# Control.net
KiCad netlist of a schematic drawn in EAGLE
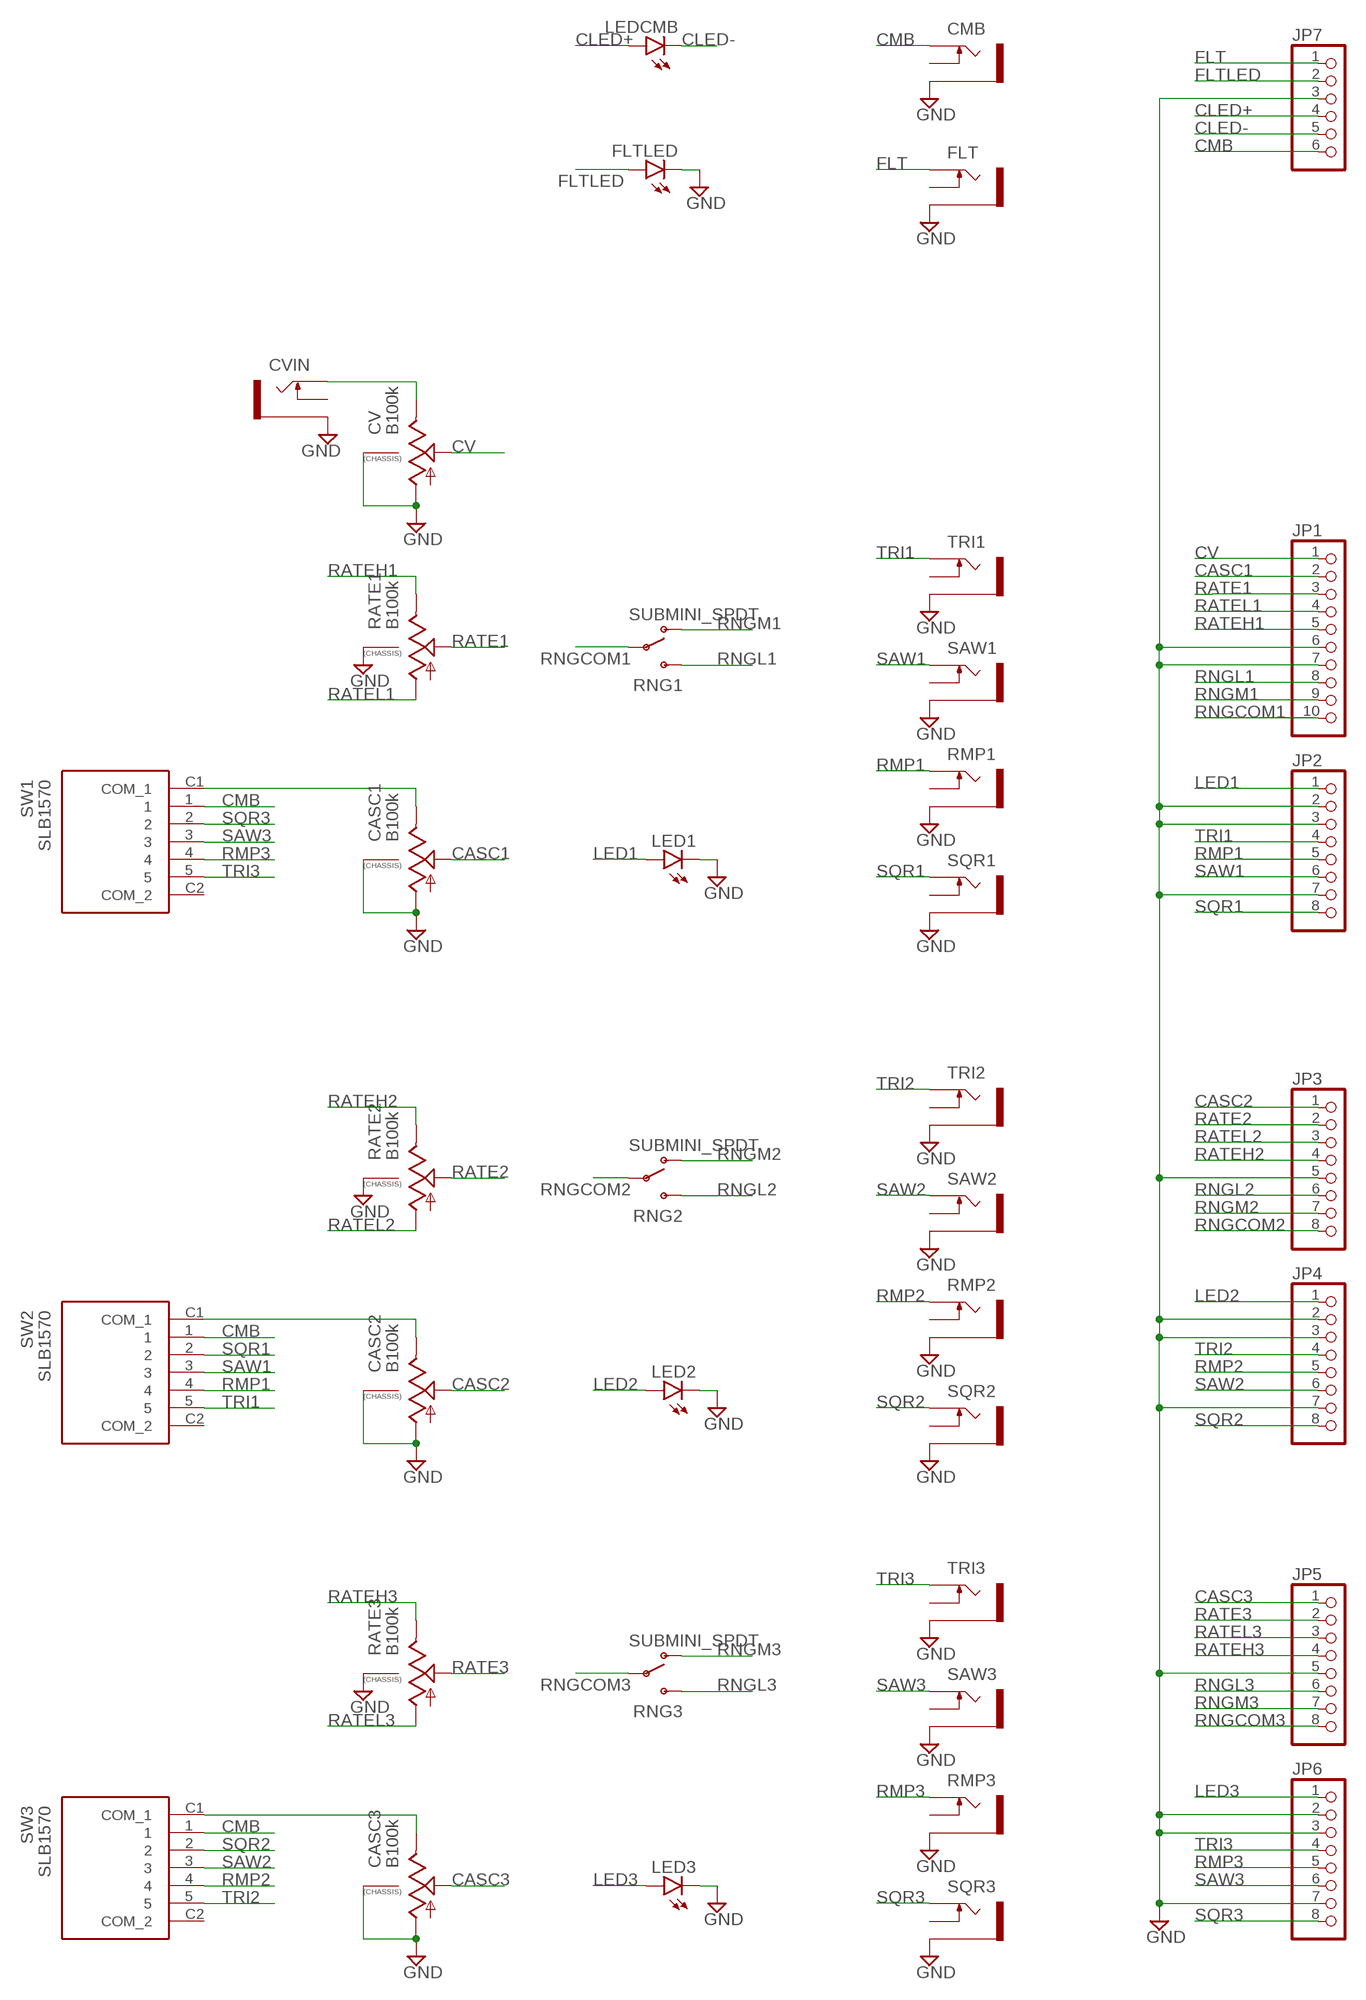
[diagram p0: schematic, sheet 1]

(export (version "E")
  (design (tool "Eeschema 10.0.6"))
  (components
    (comp (ref "CASC1")
      (value "B100k")
      (footprint "eagle-import:9MM_SNAP-IN_POT")
      (libsource (lib "eagle-import") (part "9MM_SNAP-IN_POT_CHASSIS"))
    )
    (comp (ref "CASC2")
      (value "B100k")
      (footprint "eagle-import:9MM_SNAP-IN_POT")
      (libsource (lib "eagle-import") (part "9MM_SNAP-IN_POT_CHASSIS"))
    )
    (comp (ref "CASC3")
      (value "B100k")
      (footprint "eagle-import:9MM_SNAP-IN_POT")
      (libsource (lib "eagle-import") (part "9MM_SNAP-IN_POT_CHASSIS"))
    )
    (comp (ref "CMB")
      (value "THONKICONNNEW")
      (footprint "eagle-import:WQP-PJ301M-12_JACK")
      (libsource (lib "eagle-import") (part "THONKICONNNEW"))
    )
    (comp (ref "CV")
      (value "B100k")
      (footprint "eagle-import:9MM_SNAP-IN_POT")
      (libsource (lib "eagle-import") (part "9MM_SNAP-IN_POT_CHASSIS"))
    )
    (comp (ref "CVIN")
      (value "THONKICONNNEW")
      (footprint "eagle-import:WQP-PJ301M-12_JACK")
      (libsource (lib "eagle-import") (part "THONKICONNNEW"))
    )
    (comp (ref "FLT")
      (value "THONKICONNNEW")
      (footprint "eagle-import:WQP-PJ301M-12_JACK")
      (libsource (lib "eagle-import") (part "THONKICONNNEW"))
    )
    (comp (ref "FLTLED")
      (value "LED3MM")
      (footprint "eagle-import:LED3MM")
      (libsource (lib "eagle-import") (part "LED3MM"))
    )
    (comp (ref "JP1")
      (value "PINHD-1X10")
      (footprint "eagle-import:1X10")
      (libsource (lib "eagle-import") (part "PINHD-1X10"))
    )
    (comp (ref "JP2")
      (value "PINHD-1X8")
      (footprint "eagle-import:1X08")
      (libsource (lib "eagle-import") (part "PINHD-1X8"))
    )
    (comp (ref "JP3")
      (value "PINHD-1X8")
      (footprint "eagle-import:1X08")
      (libsource (lib "eagle-import") (part "PINHD-1X8"))
    )
    (comp (ref "JP4")
      (value "PINHD-1X8")
      (footprint "eagle-import:1X08")
      (libsource (lib "eagle-import") (part "PINHD-1X8"))
    )
    (comp (ref "JP5")
      (value "PINHD-1X8")
      (footprint "eagle-import:1X08")
      (libsource (lib "eagle-import") (part "PINHD-1X8"))
    )
    (comp (ref "JP6")
      (value "PINHD-1X8")
      (footprint "eagle-import:1X08")
      (libsource (lib "eagle-import") (part "PINHD-1X8"))
    )
    (comp (ref "JP7")
      (value "PINHD-1X6")
      (footprint "eagle-import:1X06")
      (libsource (lib "eagle-import") (part "PINHD-1X6"))
    )
    (comp (ref "LED1")
      (value "LED3MM")
      (footprint "eagle-import:LED3MM")
      (libsource (lib "eagle-import") (part "LED3MM"))
    )
    (comp (ref "LED2")
      (value "LED3MM")
      (footprint "eagle-import:LED3MM")
      (libsource (lib "eagle-import") (part "LED3MM"))
    )
    (comp (ref "LED3")
      (value "LED3MM")
      (footprint "eagle-import:LED3MM")
      (libsource (lib "eagle-import") (part "LED3MM"))
    )
    (comp (ref "LEDCMB")
      (value "LED3MM")
      (footprint "eagle-import:LED3MM")
      (libsource (lib "eagle-import") (part "LED3MM"))
    )
    (comp (ref "RATE1")
      (value "B100k")
      (footprint "eagle-import:9MM_SNAP-IN_POT")
      (libsource (lib "eagle-import") (part "9MM_SNAP-IN_POT_CHASSIS"))
    )
    (comp (ref "RATE2")
      (value "B100k")
      (footprint "eagle-import:9MM_SNAP-IN_POT")
      (libsource (lib "eagle-import") (part "9MM_SNAP-IN_POT_CHASSIS"))
    )
    (comp (ref "RATE3")
      (value "B100k")
      (footprint "eagle-import:9MM_SNAP-IN_POT")
      (libsource (lib "eagle-import") (part "9MM_SNAP-IN_POT_CHASSIS"))
    )
    (comp (ref "RMP1")
      (value "THONKICONNNEW")
      (footprint "eagle-import:WQP-PJ301M-12_JACK")
      (libsource (lib "eagle-import") (part "THONKICONNNEW"))
    )
    (comp (ref "RMP2")
      (value "THONKICONNNEW")
      (footprint "eagle-import:WQP-PJ301M-12_JACK")
      (libsource (lib "eagle-import") (part "THONKICONNNEW"))
    )
    (comp (ref "RMP3")
      (value "THONKICONNNEW")
      (footprint "eagle-import:WQP-PJ301M-12_JACK")
      (libsource (lib "eagle-import") (part "THONKICONNNEW"))
    )
    (comp (ref "RNG1")
      (value "SUBMINI_SPDT")
      (footprint "eagle-import:SUBMINI_TOGGLE")
      (libsource (lib "eagle-import") (part "SUBMINI_SPDT"))
    )
    (comp (ref "RNG2")
      (value "SUBMINI_SPDT")
      (footprint "eagle-import:SUBMINI_TOGGLE")
      (libsource (lib "eagle-import") (part "SUBMINI_SPDT"))
    )
    (comp (ref "RNG3")
      (value "SUBMINI_SPDT")
      (footprint "eagle-import:SUBMINI_TOGGLE")
      (libsource (lib "eagle-import") (part "SUBMINI_SPDT"))
    )
    (comp (ref "SAW1")
      (value "THONKICONNNEW")
      (footprint "eagle-import:WQP-PJ301M-12_JACK")
      (libsource (lib "eagle-import") (part "THONKICONNNEW"))
    )
    (comp (ref "SAW2")
      (value "THONKICONNNEW")
      (footprint "eagle-import:WQP-PJ301M-12_JACK")
      (libsource (lib "eagle-import") (part "THONKICONNNEW"))
    )
    (comp (ref "SAW3")
      (value "THONKICONNNEW")
      (footprint "eagle-import:WQP-PJ301M-12_JACK")
      (libsource (lib "eagle-import") (part "THONKICONNNEW"))
    )
    (comp (ref "SQR1")
      (value "THONKICONNNEW")
      (footprint "eagle-import:WQP-PJ301M-12_JACK")
      (libsource (lib "eagle-import") (part "THONKICONNNEW"))
    )
    (comp (ref "SQR2")
      (value "THONKICONNNEW")
      (footprint "eagle-import:WQP-PJ301M-12_JACK")
      (libsource (lib "eagle-import") (part "THONKICONNNEW"))
    )
    (comp (ref "SQR3")
      (value "THONKICONNNEW")
      (footprint "eagle-import:WQP-PJ301M-12_JACK")
      (libsource (lib "eagle-import") (part "THONKICONNNEW"))
    )
    (comp (ref "SW1")
      (value "SLB1570")
      (footprint "eagle-import:SLB1570")
      (fields (field (name "MOUSER_PART_NUMBER") "642-SLB1570"))
      (libsource (lib "eagle-import") (part "SLB1570"))
    )
    (comp (ref "SW2")
      (value "SLB1570")
      (footprint "eagle-import:SLB1570")
      (fields (field (name "MOUSER_PART_NUMBER") "642-SLB1570"))
      (libsource (lib "eagle-import") (part "SLB1570"))
    )
    (comp (ref "SW3")
      (value "SLB1570")
      (footprint "eagle-import:SLB1570")
      (fields (field (name "MOUSER_PART_NUMBER") "642-SLB1570"))
      (libsource (lib "eagle-import") (part "SLB1570"))
    )
    (comp (ref "TRI1")
      (value "THONKICONNNEW")
      (footprint "eagle-import:WQP-PJ301M-12_JACK")
      (libsource (lib "eagle-import") (part "THONKICONNNEW"))
    )
    (comp (ref "TRI2")
      (value "THONKICONNNEW")
      (footprint "eagle-import:WQP-PJ301M-12_JACK")
      (libsource (lib "eagle-import") (part "THONKICONNNEW"))
    )
    (comp (ref "TRI3")
      (value "THONKICONNNEW")
      (footprint "eagle-import:WQP-PJ301M-12_JACK")
      (libsource (lib "eagle-import") (part "THONKICONNNEW"))
    )
  )
  (nets
    (net (code "1") (name "/CASC1") (class "Default")
      (node (ref "CASC1") (pin "2") (pinfunction "S_2") (pintype "passive"))
      (node (ref "JP1") (pin "2") (pinfunction "2_2") (pintype "passive"))
    )
    (net (code "2") (name "/CASC2") (class "Default")
      (node (ref "CASC2") (pin "2") (pinfunction "S_2") (pintype "passive"))
      (node (ref "JP3") (pin "1") (pinfunction "1_1") (pintype "passive"))
    )
    (net (code "3") (name "/CASC3") (class "Default")
      (node (ref "CASC3") (pin "2") (pinfunction "S_2") (pintype "passive"))
      (node (ref "JP5") (pin "1") (pinfunction "1_1") (pintype "passive"))
    )
    (net (code "4") (name "/CLED+") (class "Default")
      (node (ref "JP7") (pin "4") (pinfunction "4_4") (pintype "passive"))
      (node (ref "LEDCMB") (pin "A") (pinfunction "A_A") (pintype "passive"))
    )
    (net (code "5") (name "/CLED-") (class "Default")
      (node (ref "JP7") (pin "5") (pinfunction "5_5") (pintype "passive"))
      (node (ref "LEDCMB") (pin "K") (pinfunction "C_K") (pintype "passive"))
    )
    (net (code "6") (name "/CMB") (class "Default")
      (node (ref "CMB") (pin "P$1_TIP") (pinfunction "TIP_P$1_TIP") (pintype "passive"))
      (node (ref "JP7") (pin "6") (pinfunction "6_6") (pintype "passive"))
      (node (ref "SW1") (pin "1") (pinfunction "1_1") (pintype "bidirectional"))
      (node (ref "SW2") (pin "1") (pinfunction "1_1") (pintype "bidirectional"))
      (node (ref "SW3") (pin "1") (pinfunction "1_1") (pintype "bidirectional"))
    )
    (net (code "7") (name "/CV") (class "Default")
      (node (ref "CV") (pin "2") (pinfunction "S_2") (pintype "passive"))
      (node (ref "JP1") (pin "1") (pinfunction "1_1") (pintype "passive"))
    )
    (net (code "8") (name "/FLT") (class "Default")
      (node (ref "FLT") (pin "P$1_TIP") (pinfunction "TIP_P$1_TIP") (pintype "passive"))
      (node (ref "JP7") (pin "1") (pinfunction "1_1") (pintype "passive"))
    )
    (net (code "9") (name "/FLTLED") (class "Default")
      (node (ref "FLTLED") (pin "A") (pinfunction "A_A") (pintype "passive"))
      (node (ref "JP7") (pin "2") (pinfunction "2_2") (pintype "passive"))
    )
    (net (code "10") (name "/LED1") (class "Default")
      (node (ref "JP2") (pin "1") (pinfunction "1_1") (pintype "passive"))
      (node (ref "LED1") (pin "A") (pinfunction "A_A") (pintype "passive"))
    )
    (net (code "11") (name "/LED2") (class "Default")
      (node (ref "JP4") (pin "1") (pinfunction "1_1") (pintype "passive"))
      (node (ref "LED2") (pin "A") (pinfunction "A_A") (pintype "passive"))
    )
    (net (code "12") (name "/LED3") (class "Default")
      (node (ref "JP6") (pin "1") (pinfunction "1_1") (pintype "passive"))
      (node (ref "LED3") (pin "A") (pinfunction "A_A") (pintype "passive"))
    )
    (net (code "13") (name "/RATE1") (class "Default")
      (node (ref "JP1") (pin "3") (pinfunction "3_3") (pintype "passive"))
      (node (ref "RATE1") (pin "2") (pinfunction "S_2") (pintype "passive"))
    )
    (net (code "14") (name "/RATE2") (class "Default")
      (node (ref "JP3") (pin "2") (pinfunction "2_2") (pintype "passive"))
      (node (ref "RATE2") (pin "2") (pinfunction "S_2") (pintype "passive"))
    )
    (net (code "15") (name "/RATE3") (class "Default")
      (node (ref "JP5") (pin "2") (pinfunction "2_2") (pintype "passive"))
      (node (ref "RATE3") (pin "2") (pinfunction "S_2") (pintype "passive"))
    )
    (net (code "16") (name "/RATEH1") (class "Default")
      (node (ref "JP1") (pin "5") (pinfunction "5_5") (pintype "passive"))
      (node (ref "RATE1") (pin "3") (pinfunction "E_3") (pintype "passive"))
    )
    (net (code "17") (name "/RATEH2") (class "Default")
      (node (ref "JP3") (pin "4") (pinfunction "4_4") (pintype "passive"))
      (node (ref "RATE2") (pin "3") (pinfunction "E_3") (pintype "passive"))
    )
    (net (code "18") (name "/RATEH3") (class "Default")
      (node (ref "JP5") (pin "4") (pinfunction "4_4") (pintype "passive"))
      (node (ref "RATE3") (pin "3") (pinfunction "E_3") (pintype "passive"))
    )
    (net (code "19") (name "/RATEL1") (class "Default")
      (node (ref "JP1") (pin "4") (pinfunction "4_4") (pintype "passive"))
      (node (ref "RATE1") (pin "1") (pinfunction "A_1") (pintype "passive"))
    )
    (net (code "20") (name "/RATEL2") (class "Default")
      (node (ref "JP3") (pin "3") (pinfunction "3_3") (pintype "passive"))
      (node (ref "RATE2") (pin "1") (pinfunction "A_1") (pintype "passive"))
    )
    (net (code "21") (name "/RATEL3") (class "Default")
      (node (ref "JP5") (pin "3") (pinfunction "3_3") (pintype "passive"))
      (node (ref "RATE3") (pin "1") (pinfunction "A_1") (pintype "passive"))
    )
    (net (code "22") (name "/RMP1") (class "Default")
      (node (ref "JP2") (pin "5") (pinfunction "5_5") (pintype "passive"))
      (node (ref "RMP1") (pin "P$1_TIP") (pinfunction "TIP_P$1_TIP") (pintype "passive"))
      (node (ref "SW2") (pin "4") (pinfunction "4_4") (pintype "bidirectional"))
    )
    (net (code "23") (name "/RMP2") (class "Default")
      (node (ref "JP4") (pin "5") (pinfunction "5_5") (pintype "passive"))
      (node (ref "RMP2") (pin "P$1_TIP") (pinfunction "TIP_P$1_TIP") (pintype "passive"))
      (node (ref "SW3") (pin "4") (pinfunction "4_4") (pintype "bidirectional"))
    )
    (net (code "24") (name "/RMP3") (class "Default")
      (node (ref "JP6") (pin "5") (pinfunction "5_5") (pintype "passive"))
      (node (ref "RMP3") (pin "P$1_TIP") (pinfunction "TIP_P$1_TIP") (pintype "passive"))
      (node (ref "SW1") (pin "4") (pinfunction "4_4") (pintype "bidirectional"))
    )
    (net (code "25") (name "/RNGCOM1") (class "Default")
      (node (ref "JP1") (pin "10") (pinfunction "10_10") (pintype "passive"))
      (node (ref "RNG1") (pin "COM") (pinfunction "COMMON_COM") (pintype "passive"))
    )
    (net (code "26") (name "/RNGCOM2") (class "Default")
      (node (ref "JP3") (pin "8") (pinfunction "8_8") (pintype "passive"))
      (node (ref "RNG2") (pin "COM") (pinfunction "COMMON_COM") (pintype "passive"))
    )
    (net (code "27") (name "/RNGCOM3") (class "Default")
      (node (ref "JP5") (pin "8") (pinfunction "8_8") (pintype "passive"))
      (node (ref "RNG3") (pin "COM") (pinfunction "COMMON_COM") (pintype "passive"))
    )
    (net (code "28") (name "/RNGL1") (class "Default")
      (node (ref "JP1") (pin "8") (pinfunction "8_8") (pintype "passive"))
      (node (ref "RNG1") (pin "3") (pinfunction "S_3") (pintype "passive"))
    )
    (net (code "29") (name "/RNGL2") (class "Default")
      (node (ref "JP3") (pin "6") (pinfunction "6_6") (pintype "passive"))
      (node (ref "RNG2") (pin "3") (pinfunction "S_3") (pintype "passive"))
    )
    (net (code "30") (name "/RNGL3") (class "Default")
      (node (ref "JP5") (pin "6") (pinfunction "6_6") (pintype "passive"))
      (node (ref "RNG3") (pin "3") (pinfunction "S_3") (pintype "passive"))
    )
    (net (code "31") (name "/RNGM1") (class "Default")
      (node (ref "JP1") (pin "9") (pinfunction "9_9") (pintype "passive"))
      (node (ref "RNG1") (pin "1") (pinfunction "O_1") (pintype "passive"))
    )
    (net (code "32") (name "/RNGM2") (class "Default")
      (node (ref "JP3") (pin "7") (pinfunction "7_7") (pintype "passive"))
      (node (ref "RNG2") (pin "1") (pinfunction "O_1") (pintype "passive"))
    )
    (net (code "33") (name "/RNGM3") (class "Default")
      (node (ref "JP5") (pin "7") (pinfunction "7_7") (pintype "passive"))
      (node (ref "RNG3") (pin "1") (pinfunction "O_1") (pintype "passive"))
    )
    (net (code "34") (name "/SAW1") (class "Default")
      (node (ref "JP2") (pin "6") (pinfunction "6_6") (pintype "passive"))
      (node (ref "SAW1") (pin "P$1_TIP") (pinfunction "TIP_P$1_TIP") (pintype "passive"))
      (node (ref "SW2") (pin "3") (pinfunction "3_3") (pintype "bidirectional"))
    )
    (net (code "35") (name "/SAW2") (class "Default")
      (node (ref "JP4") (pin "6") (pinfunction "6_6") (pintype "passive"))
      (node (ref "SAW2") (pin "P$1_TIP") (pinfunction "TIP_P$1_TIP") (pintype "passive"))
      (node (ref "SW3") (pin "3") (pinfunction "3_3") (pintype "bidirectional"))
    )
    (net (code "36") (name "/SAW3") (class "Default")
      (node (ref "JP6") (pin "6") (pinfunction "6_6") (pintype "passive"))
      (node (ref "SAW3") (pin "P$1_TIP") (pinfunction "TIP_P$1_TIP") (pintype "passive"))
      (node (ref "SW1") (pin "3") (pinfunction "3_3") (pintype "bidirectional"))
    )
    (net (code "37") (name "/SQR1") (class "Default")
      (node (ref "JP2") (pin "8") (pinfunction "8_8") (pintype "passive"))
      (node (ref "SQR1") (pin "P$1_TIP") (pinfunction "TIP_P$1_TIP") (pintype "passive"))
      (node (ref "SW2") (pin "2") (pinfunction "2_2") (pintype "bidirectional"))
    )
    (net (code "38") (name "/SQR2") (class "Default")
      (node (ref "JP4") (pin "8") (pinfunction "8_8") (pintype "passive"))
      (node (ref "SQR2") (pin "P$1_TIP") (pinfunction "TIP_P$1_TIP") (pintype "passive"))
      (node (ref "SW3") (pin "2") (pinfunction "2_2") (pintype "bidirectional"))
    )
    (net (code "39") (name "/SQR3") (class "Default")
      (node (ref "JP6") (pin "8") (pinfunction "8_8") (pintype "passive"))
      (node (ref "SQR3") (pin "P$1_TIP") (pinfunction "TIP_P$1_TIP") (pintype "passive"))
      (node (ref "SW1") (pin "2") (pinfunction "2_2") (pintype "bidirectional"))
    )
    (net (code "40") (name "/TRI1") (class "Default")
      (node (ref "JP2") (pin "4") (pinfunction "4_4") (pintype "passive"))
      (node (ref "SW2") (pin "5") (pinfunction "5_5") (pintype "bidirectional"))
      (node (ref "TRI1") (pin "P$1_TIP") (pinfunction "TIP_P$1_TIP") (pintype "passive"))
    )
    (net (code "41") (name "/TRI2") (class "Default")
      (node (ref "JP4") (pin "4") (pinfunction "4_4") (pintype "passive"))
      (node (ref "SW3") (pin "5") (pinfunction "5_5") (pintype "bidirectional"))
      (node (ref "TRI2") (pin "P$1_TIP") (pinfunction "TIP_P$1_TIP") (pintype "passive"))
    )
    (net (code "42") (name "/TRI3") (class "Default")
      (node (ref "JP6") (pin "4") (pinfunction "4_4") (pintype "passive"))
      (node (ref "SW1") (pin "5") (pinfunction "5_5") (pintype "bidirectional"))
      (node (ref "TRI3") (pin "P$1_TIP") (pinfunction "TIP_P$1_TIP") (pintype "passive"))
    )
    (net (code "43") (name "GND") (class "Default")
      (node (ref "CASC1") (pin "1") (pinfunction "A_1") (pintype "passive"))
      (node (ref "CASC1") (pin "CHASSIS1") (pinfunction "P$1_CHASSIS1") (pintype "passive"))
      (node (ref "CASC1") (pin "CHASSIS2") (pinfunction "P$1_CHASSIS2") (pintype "passive"))
      (node (ref "CASC2") (pin "1") (pinfunction "A_1") (pintype "passive"))
      (node (ref "CASC2") (pin "CHASSIS1") (pinfunction "P$1_CHASSIS1") (pintype "passive"))
      (node (ref "CASC2") (pin "CHASSIS2") (pinfunction "P$1_CHASSIS2") (pintype "passive"))
      (node (ref "CASC3") (pin "1") (pinfunction "A_1") (pintype "passive"))
      (node (ref "CASC3") (pin "CHASSIS1") (pinfunction "P$1_CHASSIS1") (pintype "passive"))
      (node (ref "CASC3") (pin "CHASSIS2") (pinfunction "P$1_CHASSIS2") (pintype "passive"))
      (node (ref "CMB") (pin "P$3_SLEEVE") (pinfunction "SLEEVE_P$3_SLEEVE") (pintype "passive"))
      (node (ref "CV") (pin "1") (pinfunction "A_1") (pintype "passive"))
      (node (ref "CV") (pin "CHASSIS1") (pinfunction "P$1_CHASSIS1") (pintype "passive"))
      (node (ref "CV") (pin "CHASSIS2") (pinfunction "P$1_CHASSIS2") (pintype "passive"))
      (node (ref "CVIN") (pin "P$3_SLEEVE") (pinfunction "SLEEVE_P$3_SLEEVE") (pintype "passive"))
      (node (ref "FLT") (pin "P$3_SLEEVE") (pinfunction "SLEEVE_P$3_SLEEVE") (pintype "passive"))
      (node (ref "FLTLED") (pin "K") (pinfunction "C_K") (pintype "passive"))
      (node (ref "JP1") (pin "6") (pinfunction "6_6") (pintype "passive"))
      (node (ref "JP1") (pin "7") (pinfunction "7_7") (pintype "passive"))
      (node (ref "JP2") (pin "2") (pinfunction "2_2") (pintype "passive"))
      (node (ref "JP2") (pin "3") (pinfunction "3_3") (pintype "passive"))
      (node (ref "JP2") (pin "7") (pinfunction "7_7") (pintype "passive"))
      (node (ref "JP3") (pin "5") (pinfunction "5_5") (pintype "passive"))
      (node (ref "JP4") (pin "2") (pinfunction "2_2") (pintype "passive"))
      (node (ref "JP4") (pin "3") (pinfunction "3_3") (pintype "passive"))
      (node (ref "JP4") (pin "7") (pinfunction "7_7") (pintype "passive"))
      (node (ref "JP5") (pin "5") (pinfunction "5_5") (pintype "passive"))
      (node (ref "JP6") (pin "2") (pinfunction "2_2") (pintype "passive"))
      (node (ref "JP6") (pin "3") (pinfunction "3_3") (pintype "passive"))
      (node (ref "JP6") (pin "7") (pinfunction "7_7") (pintype "passive"))
      (node (ref "JP7") (pin "3") (pinfunction "3_3") (pintype "passive"))
      (node (ref "LED1") (pin "K") (pinfunction "C_K") (pintype "passive"))
      (node (ref "LED2") (pin "K") (pinfunction "C_K") (pintype "passive"))
      (node (ref "LED3") (pin "K") (pinfunction "C_K") (pintype "passive"))
      (node (ref "RATE1") (pin "CHASSIS1") (pinfunction "P$1_CHASSIS1") (pintype "passive"))
      (node (ref "RATE1") (pin "CHASSIS2") (pinfunction "P$1_CHASSIS2") (pintype "passive"))
      (node (ref "RATE2") (pin "CHASSIS1") (pinfunction "P$1_CHASSIS1") (pintype "passive"))
      (node (ref "RATE2") (pin "CHASSIS2") (pinfunction "P$1_CHASSIS2") (pintype "passive"))
      (node (ref "RATE3") (pin "CHASSIS1") (pinfunction "P$1_CHASSIS1") (pintype "passive"))
      (node (ref "RATE3") (pin "CHASSIS2") (pinfunction "P$1_CHASSIS2") (pintype "passive"))
      (node (ref "RMP1") (pin "P$3_SLEEVE") (pinfunction "SLEEVE_P$3_SLEEVE") (pintype "passive"))
      (node (ref "RMP2") (pin "P$3_SLEEVE") (pinfunction "SLEEVE_P$3_SLEEVE") (pintype "passive"))
      (node (ref "RMP3") (pin "P$3_SLEEVE") (pinfunction "SLEEVE_P$3_SLEEVE") (pintype "passive"))
      (node (ref "SAW1") (pin "P$3_SLEEVE") (pinfunction "SLEEVE_P$3_SLEEVE") (pintype "passive"))
      (node (ref "SAW2") (pin "P$3_SLEEVE") (pinfunction "SLEEVE_P$3_SLEEVE") (pintype "passive"))
      (node (ref "SAW3") (pin "P$3_SLEEVE") (pinfunction "SLEEVE_P$3_SLEEVE") (pintype "passive"))
      (node (ref "SQR1") (pin "P$3_SLEEVE") (pinfunction "SLEEVE_P$3_SLEEVE") (pintype "passive"))
      (node (ref "SQR2") (pin "P$3_SLEEVE") (pinfunction "SLEEVE_P$3_SLEEVE") (pintype "passive"))
      (node (ref "SQR3") (pin "P$3_SLEEVE") (pinfunction "SLEEVE_P$3_SLEEVE") (pintype "passive"))
      (node (ref "TRI1") (pin "P$3_SLEEVE") (pinfunction "SLEEVE_P$3_SLEEVE") (pintype "passive"))
      (node (ref "TRI2") (pin "P$3_SLEEVE") (pinfunction "SLEEVE_P$3_SLEEVE") (pintype "passive"))
      (node (ref "TRI3") (pin "P$3_SLEEVE") (pinfunction "SLEEVE_P$3_SLEEVE") (pintype "passive"))
    )
    (net (code "44") (name "Net-(CASC1-E)") (class "Default")
      (node (ref "CASC1") (pin "3") (pinfunction "E_3") (pintype "passive"))
      (node (ref "SW1") (pin "C1") (pinfunction "COM_1_C1") (pintype "bidirectional"))
    )
    (net (code "45") (name "Net-(CASC2-E)") (class "Default")
      (node (ref "CASC2") (pin "3") (pinfunction "E_3") (pintype "passive"))
      (node (ref "SW2") (pin "C1") (pinfunction "COM_1_C1") (pintype "bidirectional"))
    )
    (net (code "46") (name "Net-(CASC3-E)") (class "Default")
      (node (ref "CASC3") (pin "3") (pinfunction "E_3") (pintype "passive"))
      (node (ref "SW3") (pin "C1") (pinfunction "COM_1_C1") (pintype "bidirectional"))
    )
    (net (code "47") (name "Net-(CV-E)") (class "Default")
      (node (ref "CV") (pin "3") (pinfunction "E_3") (pintype "passive"))
      (node (ref "CVIN") (pin "P$1_TIP") (pinfunction "TIP_P$1_TIP") (pintype "passive"))
    )
    (net (code "48") (name "unconnected-(CMB-SWITCH-PadP$2_SWITCH)") (class "Default")
      (node (ref "CMB") (pin "P$2_SWITCH") (pinfunction "SWITCH_P$2_SWITCH") (pintype "passive"))
    )
    (net (code "49") (name "unconnected-(CVIN-SWITCH-PadP$2_SWITCH)") (class "Default")
      (node (ref "CVIN") (pin "P$2_SWITCH") (pinfunction "SWITCH_P$2_SWITCH") (pintype "passive"))
    )
    (net (code "50") (name "unconnected-(FLT-SWITCH-PadP$2_SWITCH)") (class "Default")
      (node (ref "FLT") (pin "P$2_SWITCH") (pinfunction "SWITCH_P$2_SWITCH") (pintype "passive"))
    )
    (net (code "51") (name "unconnected-(RMP1-SWITCH-PadP$2_SWITCH)") (class "Default")
      (node (ref "RMP1") (pin "P$2_SWITCH") (pinfunction "SWITCH_P$2_SWITCH") (pintype "passive"))
    )
    (net (code "52") (name "unconnected-(RMP2-SWITCH-PadP$2_SWITCH)") (class "Default")
      (node (ref "RMP2") (pin "P$2_SWITCH") (pinfunction "SWITCH_P$2_SWITCH") (pintype "passive"))
    )
    (net (code "53") (name "unconnected-(RMP3-SWITCH-PadP$2_SWITCH)") (class "Default")
      (node (ref "RMP3") (pin "P$2_SWITCH") (pinfunction "SWITCH_P$2_SWITCH") (pintype "passive"))
    )
    (net (code "54") (name "unconnected-(SAW1-SWITCH-PadP$2_SWITCH)") (class "Default")
      (node (ref "SAW1") (pin "P$2_SWITCH") (pinfunction "SWITCH_P$2_SWITCH") (pintype "passive"))
    )
    (net (code "55") (name "unconnected-(SAW2-SWITCH-PadP$2_SWITCH)") (class "Default")
      (node (ref "SAW2") (pin "P$2_SWITCH") (pinfunction "SWITCH_P$2_SWITCH") (pintype "passive"))
    )
    (net (code "56") (name "unconnected-(SAW3-SWITCH-PadP$2_SWITCH)") (class "Default")
      (node (ref "SAW3") (pin "P$2_SWITCH") (pinfunction "SWITCH_P$2_SWITCH") (pintype "passive"))
    )
    (net (code "57") (name "unconnected-(SQR1-SWITCH-PadP$2_SWITCH)") (class "Default")
      (node (ref "SQR1") (pin "P$2_SWITCH") (pinfunction "SWITCH_P$2_SWITCH") (pintype "passive"))
    )
    (net (code "58") (name "unconnected-(SQR2-SWITCH-PadP$2_SWITCH)") (class "Default")
      (node (ref "SQR2") (pin "P$2_SWITCH") (pinfunction "SWITCH_P$2_SWITCH") (pintype "passive"))
    )
    (net (code "59") (name "unconnected-(SQR3-SWITCH-PadP$2_SWITCH)") (class "Default")
      (node (ref "SQR3") (pin "P$2_SWITCH") (pinfunction "SWITCH_P$2_SWITCH") (pintype "passive"))
    )
    (net (code "60") (name "unconnected-(SW1-COM_2-PadC2)") (class "Default")
      (node (ref "SW1") (pin "C2") (pinfunction "COM_2_C2") (pintype "bidirectional"))
    )
    (net (code "61") (name "unconnected-(SW2-COM_2-PadC2)") (class "Default")
      (node (ref "SW2") (pin "C2") (pinfunction "COM_2_C2") (pintype "bidirectional"))
    )
    (net (code "62") (name "unconnected-(SW3-COM_2-PadC2)") (class "Default")
      (node (ref "SW3") (pin "C2") (pinfunction "COM_2_C2") (pintype "bidirectional"))
    )
    (net (code "63") (name "unconnected-(TRI1-SWITCH-PadP$2_SWITCH)") (class "Default")
      (node (ref "TRI1") (pin "P$2_SWITCH") (pinfunction "SWITCH_P$2_SWITCH") (pintype "passive"))
    )
    (net (code "64") (name "unconnected-(TRI2-SWITCH-PadP$2_SWITCH)") (class "Default")
      (node (ref "TRI2") (pin "P$2_SWITCH") (pinfunction "SWITCH_P$2_SWITCH") (pintype "passive"))
    )
    (net (code "65") (name "unconnected-(TRI3-SWITCH-PadP$2_SWITCH)") (class "Default")
      (node (ref "TRI3") (pin "P$2_SWITCH") (pinfunction "SWITCH_P$2_SWITCH") (pintype "passive"))
    )
  )
)
